# NuclearSMR-1_2.net
KiCad netlist of a schematic drawn in EasyEDA Pro
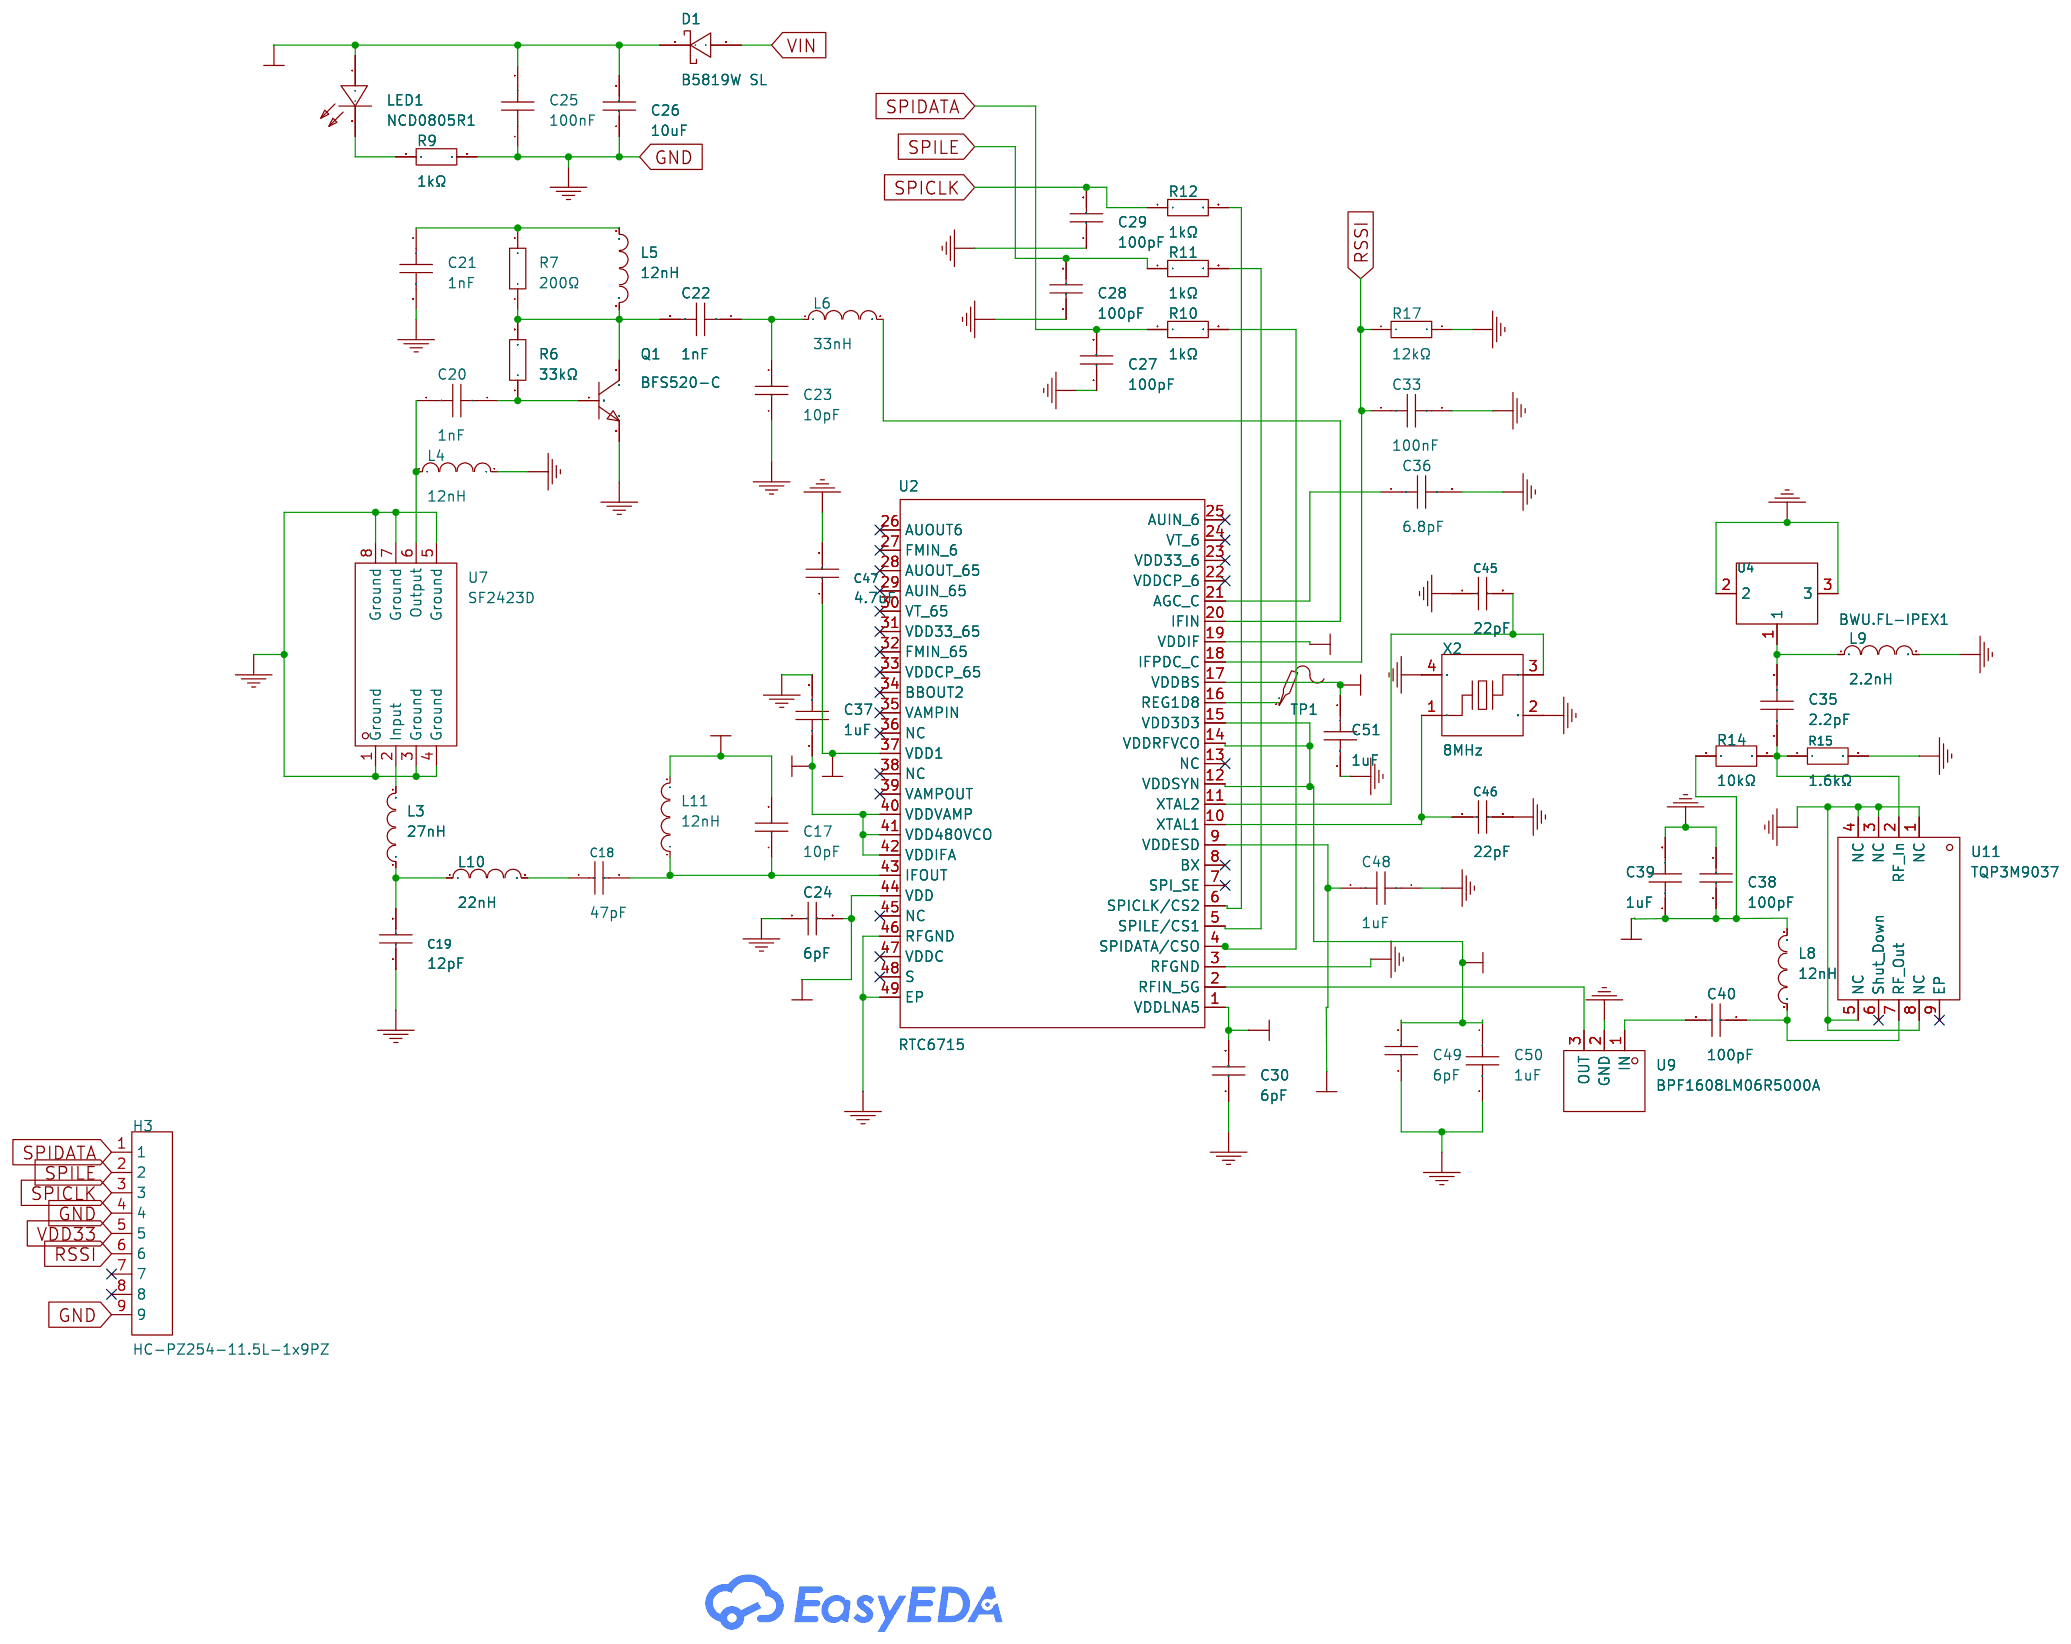
[diagram p0: schematic sheet]

(export (version "E")
  (design (tool "Eeschema 10.0.6"))
  (components
    (comp (ref "C17")
      (value "10pF")
      (footprint "easyedapro:C0402")
      (fields
        (field (name "Manufacturer Part") "CC0402JRNPO9BN100")
        (field (name "Manufacturer") "YAGEO(国巨)")
      )
      (libsource (lib "easyedapro") (part "CC0402JRNPO9BN100"))
    )
    (comp (ref "C18")
      (value "47pF")
      (footprint "easyedapro:C0402")
      (fields
        (field (name "Manufacturer Part") "CC0402JRNPO9BN470")
        (field (name "Manufacturer") "YAGEO(国巨)")
      )
      (libsource (lib "easyedapro") (part "CC0402JRNPO9BN470"))
    )
    (comp (ref "C19")
      (value "12pF")
      (footprint "easyedapro:C0402")
      (fields
        (field (name "Manufacturer Part") "GRM1555C1H120JA01D")
        (field (name "Manufacturer") "muRata(村田)")
      )
      (libsource (lib "easyedapro") (part "GRM1555C1H120JA01D"))
    )
    (comp (ref "C20")
      (value "1nF")
      (footprint "easyedapro:C0402")
      (fields
        (field (name "Manufacturer Part") "GRM155R71H102KA01D")
        (field (name "Manufacturer") "muRata(村田)")
      )
      (libsource (lib "easyedapro") (part "GRM155R71H102KA01D"))
    )
    (comp (ref "C21")
      (value "1nF")
      (footprint "easyedapro:C0402")
      (fields
        (field (name "Manufacturer Part") "GRM155R71H102KA01D")
        (field (name "Manufacturer") "muRata(村田)")
      )
      (libsource (lib "easyedapro") (part "GRM155R71H102KA01D"))
    )
    (comp (ref "C22")
      (value "1nF")
      (footprint "easyedapro:C0402")
      (fields
        (field (name "Manufacturer Part") "GRM155R71H102KA01D")
        (field (name "Manufacturer") "muRata(村田)")
      )
      (libsource (lib "easyedapro") (part "GRM155R71H102KA01D"))
    )
    (comp (ref "C23")
      (value "10pF")
      (footprint "easyedapro:C0402")
      (fields
        (field (name "Manufacturer Part") "GRM1555C1H100JA01D")
        (field (name "Manufacturer") "muRata(村田)")
      )
      (libsource (lib "easyedapro") (part "GRM1555C1H100JA01D"))
    )
    (comp (ref "C24")
      (value "6pF")
      (footprint "easyedapro:C0402")
      (fields (field (name "Manufacturer Part") "0402CG6R0C500NT") (field (name "Manufacturer") "FH(风华)"))
      (libsource (lib "easyedapro") (part "0402CG6R0C500NT"))
    )
    (comp (ref "C25")
      (value "100nF")
      (footprint "easyedapro:C0402")
      (fields
        (field (name "Manufacturer Part") "CL05B104KO5NNNC")
        (field (name "Manufacturer") "SAMSUNG(三星)")
      )
      (libsource (lib "easyedapro") (part "CL05B104KO5NNNC"))
    )
    (comp (ref "C26")
      (value "10uF")
      (fields
        (field (name "Manufacturer Part") "GRM155R60J106ME44D")
        (field (name "Manufacturer") "muRata(村田)")
      )
      (libsource (lib "easyedapro") (part "CL05A106MQ5NUNC"))
    )
    (comp (ref "C27")
      (value "100pF")
      (footprint "easyedapro:C0402")
      (fields
        (field (name "Manufacturer Part") "GRM1555C1H101JA01D")
        (field (name "Manufacturer") "muRata(村田)")
      )
      (libsource (lib "easyedapro") (part "GRM1555C1H101JA01D"))
    )
    (comp (ref "C28")
      (value "100pF")
      (footprint "easyedapro:C0402")
      (fields
        (field (name "Manufacturer Part") "GRM1555C1H101JA01D")
        (field (name "Manufacturer") "muRata(村田)")
      )
      (libsource (lib "easyedapro") (part "GRM1555C1H101JA01D"))
    )
    (comp (ref "C29")
      (value "100pF")
      (footprint "easyedapro:C0402")
      (fields
        (field (name "Manufacturer Part") "GRM1555C1H101JA01D")
        (field (name "Manufacturer") "muRata(村田)")
      )
      (libsource (lib "easyedapro") (part "GRM1555C1H101JA01D"))
    )
    (comp (ref "C30")
      (value "6pF")
      (footprint "easyedapro:C0402")
      (fields (field (name "Manufacturer Part") "0402CG6R0C500NT") (field (name "Manufacturer") "FH(风华)"))
      (libsource (lib "easyedapro") (part "0402CG6R0C500NT"))
    )
    (comp (ref "C33")
      (value "100nF")
      (footprint "easyedapro:C0402")
      (fields
        (field (name "Manufacturer Part") "CL05B104KO5NNNC")
        (field (name "Manufacturer") "SAMSUNG(三星)")
      )
      (libsource (lib "easyedapro") (part "CL05B104KO5NNNC"))
    )
    (comp (ref "C35")
      (value "2.2pF")
      (footprint "easyedapro:C0402")
      (fields
        (field (name "Manufacturer Part") "GJM1555C1H2R2BB01D")
        (field (name "Manufacturer") "muRata(村田)")
      )
      (libsource (lib "easyedapro") (part "GJM1555C1H2R2BB01D"))
    )
    (comp (ref "C36")
      (value "6.8pF")
      (footprint "easyedapro:C0402")
      (fields
        (field (name "Manufacturer Part") "CC0402CRNPO9BN6R8")
        (field (name "Manufacturer") "YAGEO(国巨)")
      )
      (libsource (lib "easyedapro") (part "CC0402CRNPO9BN6R8"))
    )
    (comp (ref "C37")
      (value "1uF")
      (footprint "easyedapro:C0402")
      (fields
        (field (name "Manufacturer Part") "CL05A105KA5NQNC")
        (field (name "Manufacturer") "SAMSUNG(三星)")
      )
      (libsource (lib "easyedapro") (part "CL05A105KA5NQNC"))
    )
    (comp (ref "C38")
      (value "100pF")
      (footprint "easyedapro:C0402")
      (fields
        (field (name "Manufacturer Part") "GRM1555C1H101JA01D")
        (field (name "Manufacturer") "muRata(村田)")
      )
      (libsource (lib "easyedapro") (part "GRM1555C1H101JA01D"))
    )
    (comp (ref "C39")
      (value "1uF")
      (footprint "easyedapro:C0402")
      (fields
        (field (name "Manufacturer Part") "CL05A105KA5NQNC")
        (field (name "Manufacturer") "SAMSUNG(三星)")
      )
      (libsource (lib "easyedapro") (part "CL05A105KA5NQNC"))
    )
    (comp (ref "C40")
      (value "100pF")
      (footprint "easyedapro:C0402")
      (fields
        (field (name "Manufacturer Part") "GRM1555C1H101JA01D")
        (field (name "Manufacturer") "muRata(村田)")
      )
      (libsource (lib "easyedapro") (part "GRM1555C1H101JA01D"))
    )
    (comp (ref "C45")
      (value "22pF")
      (footprint "easyedapro:C0402")
      (fields
        (field (name "Manufacturer Part") "CC0402JRNPO9BN220")
        (field (name "Manufacturer") "YAGEO(国巨)")
      )
      (libsource (lib "easyedapro") (part "CC0402JRNPO9BN220"))
    )
    (comp (ref "C46")
      (value "22pF")
      (footprint "easyedapro:C0402")
      (fields
        (field (name "Manufacturer Part") "CC0402JRNPO9BN220")
        (field (name "Manufacturer") "YAGEO(国巨)")
      )
      (libsource (lib "easyedapro") (part "CC0402JRNPO9BN220"))
    )
    (comp (ref "C47")
      (value "4.7uF")
      (footprint "easyedapro:C0402")
      (fields
        (field (name "Manufacturer Part") "CL05A475MP5NRNC")
        (field (name "Manufacturer") "SAMSUNG(三星)")
      )
      (libsource (lib "easyedapro") (part "CL05A475MP5NRNC"))
    )
    (comp (ref "C48")
      (value "1uF")
      (footprint "easyedapro:C0402")
      (fields
        (field (name "Manufacturer Part") "CL05A105KA5NQNC")
        (field (name "Manufacturer") "SAMSUNG(三星)")
      )
      (libsource (lib "easyedapro") (part "CL05A105KA5NQNC"))
    )
    (comp (ref "C49")
      (value "6pF")
      (footprint "easyedapro:C0402")
      (fields (field (name "Manufacturer Part") "0402CG6R0C500NT") (field (name "Manufacturer") "FH(风华)"))
      (libsource (lib "easyedapro") (part "0402CG6R0C500NT"))
    )
    (comp (ref "C50")
      (value "1uF")
      (footprint "easyedapro:C0402")
      (fields
        (field (name "Manufacturer Part") "CL05A105KA5NQNC")
        (field (name "Manufacturer") "SAMSUNG(三星)")
      )
      (libsource (lib "easyedapro") (part "CL05A105KA5NQNC"))
    )
    (comp (ref "C51")
      (value "1uF")
      (footprint "easyedapro:C0402")
      (fields
        (field (name "Manufacturer Part") "CL05A105KA5NQNC")
        (field (name "Manufacturer") "SAMSUNG(三星)")
      )
      (libsource (lib "easyedapro") (part "CL05A105KA5NQNC"))
    )
    (comp (ref "D1")
      (value "B5819W SL")
      (footprint "easyedapro:SOD-123_L2.7-W1.6-LS3.7-RD-1")
      (description "Forward Voltage (Vf@If):600mV@1A Reverse Voltage (Vr):40V Rectified Current:1A")
      (fields (field (name "Manufacturer") "CJ(江苏长电/长晶)"))
      (libsource (lib "easyedapro") (part "B5819W_C8598"))
    )
    (comp (ref "H3")
      (value "HC-PZ254-11.5L-1x9PZ")
      (footprint "easyedapro:HDR-TH_9P-P2.54-V-M")
      (fields (field (name "Manufacturer") "HC(虹成电子)"))
      (libsource (lib "easyedapro") (part "HC-PZ254-11.5L-1X9PZ"))
    )
    (comp (ref "L3")
      (value "27nH")
      (footprint "easyedapro:L0402-RD")
      (fields (field (name "Manufacturer Part") "LQG15HS27NJ02D") (field (name "Manufacturer") "muRata(村田)"))
      (libsource (lib "easyedapro") (part "LQG15HS27NJ02D"))
    )
    (comp (ref "L4")
      (value "12nH")
      (footprint "easyedapro:L0402")
      (fields (field (name "Manufacturer Part") "LQW15AN12NG00D") (field (name "Manufacturer") "muRata(村田)"))
      (libsource (lib "easyedapro") (part "LQW15AN12NG00D"))
    )
    (comp (ref "L5")
      (value "12nH")
      (footprint "easyedapro:L0402")
      (fields (field (name "Manufacturer Part") "LQW15AN12NG00D") (field (name "Manufacturer") "muRata(村田)"))
      (libsource (lib "easyedapro") (part "LQW15AN12NG00D"))
    )
    (comp (ref "L6")
      (value "33nH")
      (footprint "easyedapro:L0402")
      (fields (field (name "Manufacturer Part") "LQG15HS33NJ02D") (field (name "Manufacturer") "muRata(村田)"))
      (libsource (lib "easyedapro") (part "LQG15HS33NJ02D"))
    )
    (comp (ref "L8")
      (value "12nH")
      (footprint "easyedapro:L0402")
      (fields (field (name "Manufacturer Part") "LQW15AN12NG00D") (field (name "Manufacturer") "muRata(村田)"))
      (libsource (lib "easyedapro") (part "LQW15AN12NG00D"))
    )
    (comp (ref "L9")
      (value "2.2nH")
      (footprint "easyedapro:L0402")
      (fields (field (name "Manufacturer Part") "LQG15HS2N2S02D") (field (name "Manufacturer") "muRata(村田)"))
      (libsource (lib "easyedapro") (part "LQG15HS2N2S02D"))
    )
    (comp (ref "L10")
      (value "22nH")
      (footprint "easyedapro:L0402")
      (fields (field (name "Manufacturer Part") "LQW15AN22NJ00D") (field (name "Manufacturer") "muRata(村田)"))
      (libsource (lib "easyedapro") (part "LQW15AN22NJ00D"))
    )
    (comp (ref "L11")
      (value "12nH")
      (footprint "easyedapro:L0402")
      (fields (field (name "Manufacturer Part") "LQW15AN12NG00D") (field (name "Manufacturer") "muRata(村田)"))
      (libsource (lib "easyedapro") (part "LQW15AN12NG00D"))
    )
    (comp (ref "LED1")
      (value "NCD0805R1")
      (footprint "easyedapro:LED0805-R-RD")
      (fields (field (name "Manufacturer") "国星光电"))
      (libsource (lib "easyedapro") (part "FC-2012HRK-620D"))
    )
    (comp (ref "Q1")
      (value "BFS520-C")
      (footprint "easyedapro:SOT-323-3_L2.0-W1.3-P1.30-LS2.3-BR")
      (fields (field (name "Manufacturer") "Slkor(萨科微)"))
      (libsource (lib "easyedapro") (part "BFS520-C"))
    )
    (comp (ref "R6")
      (value "33kΩ")
      (footprint "easyedapro:R0402")
      (fields (field (name "Manufacturer Part") "RC0402FR-0733KL") (field (name "Manufacturer") "YAGEO(国巨)"))
      (libsource (lib "easyedapro") (part "RC0402FR-0733KL"))
    )
    (comp (ref "R7")
      (value "200Ω")
      (footprint "easyedapro:R0402")
      (fields (field (name "Manufacturer Part") "RC0402FR-07200RL") (field (name "Manufacturer") "YAGEO(国巨)"))
      (libsource (lib "easyedapro") (part "RC0402FR-07200RL"))
    )
    (comp (ref "R9")
      (value "1kΩ")
      (footprint "easyedapro:R0402")
      (fields (field (name "Manufacturer Part") "RC0402FR-071KL") (field (name "Manufacturer") "YAGEO(国巨)"))
      (libsource (lib "easyedapro") (part "RC0402FR-071KL"))
    )
    (comp (ref "R10")
      (value "1kΩ")
      (footprint "easyedapro:R0402")
      (fields (field (name "Manufacturer Part") "RC0402FR-071KL") (field (name "Manufacturer") "YAGEO(国巨)"))
      (libsource (lib "easyedapro") (part "RC0402FR-071KL"))
    )
    (comp (ref "R11")
      (value "1kΩ")
      (footprint "easyedapro:R0402")
      (fields (field (name "Manufacturer Part") "RC0402FR-071KL") (field (name "Manufacturer") "YAGEO(国巨)"))
      (libsource (lib "easyedapro") (part "RC0402FR-071KL"))
    )
    (comp (ref "R12")
      (value "1kΩ")
      (footprint "easyedapro:R0402")
      (fields (field (name "Manufacturer Part") "RC0402FR-071KL") (field (name "Manufacturer") "YAGEO(国巨)"))
      (libsource (lib "easyedapro") (part "RC0402FR-071KL"))
    )
    (comp (ref "R14")
      (value "10kΩ")
      (footprint "easyedapro:R0402")
      (fields (field (name "Manufacturer Part") "FRC0402F1002TS") (field (name "Manufacturer") "FOJAN(富捷)"))
      (libsource (lib "easyedapro") (part "FRC0402F1002TS"))
    )
    (comp (ref "R15")
      (value "1.6kΩ")
      (footprint "easyedapro:R0402")
      (fields
        (field (name "Manufacturer Part") "0402WGF1601TCE")
        (field (name "Manufacturer") "UNI-ROYAL(厚声)")
      )
      (libsource (lib "easyedapro") (part "0402WGF1601TCE"))
    )
    (comp (ref "R17")
      (value "12kΩ")
      (footprint "easyedapro:R0402")
      (fields (field (name "Manufacturer Part") "RTT021202FTH") (field (name "Manufacturer") "RALEC(旺诠)"))
      (libsource (lib "easyedapro") (part "RTT021202FTH"))
    )
    (comp (ref "TP1")
      (value "~")
      (footprint "easyedapro:Test-Point-0.5mm")
      (description "Test Point 测试点")
      (libsource (lib "easyedapro") (part "Test-Point"))
    )
    (comp (ref "U2") (value "RTC6715") (libsource (lib "easyedapro") (part "RTC6715")))
    (comp (ref "U4")
      (value "BWU.FL-IPEX1")
      (footprint "easyedapro:IPEX-SMD_BWIPX-1-001E")
      (fields (field (name "Manufacturer") "BAT WIRELESS(蝙蝠无线)"))
      (libsource (lib "easyedapro") (part "BWU.FL-IPEX1"))
    )
    (comp (ref "U7")
      (value "SF2423D")
      (footprint "easyedapro:FILTER-SMD_8P-L3.8-W3.8-P1.27-BL")
      (fields (field (name "Manufacturer") "muRata(村田)"))
      (libsource (lib "easyedapro") (part "SF2423D"))
    )
    (comp (ref "U9")
      (value "BPF1608LM06R5000A")
      (footprint "easyedapro:FILTER-SMD_3P-L1.6-W0.8-L")
      (description "Bandwidth:800MHz Filter Type:Bandpass Insertion Loss:0.6dB")
      (fields (field (name "Manufacturer") "YAGEO(国巨)"))
      (libsource (lib "easyedapro") (part "BPF1608LM06R5000A"))
    )
    (comp (ref "U11")
      (value "TQP3M9037")
      (footprint "easyedapro:DFN-8_L2.0-W2.0-P0.50-BL-EP")
      (fields (field (name "Manufacturer") "Qorvo"))
      (libsource (lib "easyedapro") (part "TQP3M9037"))
    )
    (comp (ref "X2")
      (value "8MHz")
      (footprint "easyedapro:CRYSTAL-SMD_4P-L3.2-W2.5-BL")
      (fields (field (name "Manufacturer Part") "K3A080001210") (field (name "Manufacturer") "KYX(凯越翔)"))
      (libsource (lib "easyedapro") (part "K3A080001210"))
    )
  )
  (nets
    (net (code "1") (name "GND") (class "Default")
      (node (ref "C19") (pin "1") (pinfunction "1_1") (pintype "input"))
      (node (ref "C21") (pin "2") (pinfunction "2_2") (pintype "unspecified"))
      (node (ref "C23") (pin "1") (pinfunction "1_1") (pintype "input"))
      (node (ref "C24") (pin "1") (pinfunction "1_1") (pintype "input"))
      (node (ref "C25") (pin "1") (pinfunction "1_1") (pintype "unspecified"))
      (node (ref "C26") (pin "1") (pinfunction "1_1") (pintype "input"))
      (node (ref "C27") (pin "1") (pinfunction "1_1") (pintype "input"))
      (node (ref "C28") (pin "1") (pinfunction "1_1") (pintype "input"))
      (node (ref "C29") (pin "1") (pinfunction "1_1") (pintype "input"))
      (node (ref "C30") (pin "1") (pinfunction "1_1") (pintype "input"))
      (node (ref "C33") (pin "2") (pinfunction "2_2") (pintype "unspecified"))
      (node (ref "C36") (pin "2") (pinfunction "2_2") (pintype "unspecified"))
      (node (ref "C37") (pin "2") (pinfunction "2_2") (pintype "unspecified"))
      (node (ref "C38") (pin "2") (pinfunction "2_2") (pintype "input"))
      (node (ref "C39") (pin "2") (pinfunction "2_2") (pintype "unspecified"))
      (node (ref "C45") (pin "1") (pinfunction "1_1") (pintype "input"))
      (node (ref "C46") (pin "2") (pinfunction "2_2") (pintype "input"))
      (node (ref "C47") (pin "2") (pinfunction "2_2") (pintype "input"))
      (node (ref "C48") (pin "1") (pinfunction "1_1") (pintype "unspecified"))
      (node (ref "C49") (pin "1") (pinfunction "1_1") (pintype "input"))
      (node (ref "C50") (pin "2") (pinfunction "2_2") (pintype "unspecified"))
      (node (ref "C51") (pin "2") (pinfunction "2_2") (pintype "unspecified"))
      (node (ref "H3") (pin "4") (pinfunction "4_4") (pintype "unspecified"))
      (node (ref "H3") (pin "9") (pinfunction "9_9") (pintype "unspecified"))
      (node (ref "L4") (pin "2") (pinfunction "2_2") (pintype "unspecified"))
      (node (ref "L9") (pin "2") (pinfunction "2_2") (pintype "unspecified"))
      (node (ref "Q1") (pin "2") (pinfunction "E_2") (pintype "input"))
      (node (ref "R15") (pin "2") (pinfunction "2_2") (pintype "input"))
      (node (ref "R17") (pin "2") (pinfunction "2_2") (pintype "input"))
      (node (ref "R9") (pin "2") (pinfunction "2_2") (pintype "input"))
      (node (ref "U11") (pin "1") (pinfunction "NC_1") (pintype "unspecified"))
      (node (ref "U11") (pin "3") (pinfunction "NC_3") (pintype "unspecified"))
      (node (ref "U11") (pin "4") (pinfunction "NC_4") (pintype "unspecified"))
      (node (ref "U11") (pin "5") (pinfunction "NC_5") (pintype "unspecified"))
      (node (ref "U11") (pin "8") (pinfunction "NC_8") (pintype "unspecified"))
      (node (ref "U2") (pin "3") (pinfunction "RFGND_3") (pintype "unspecified"))
      (node (ref "U2") (pin "46") (pinfunction "RFGND_46") (pintype "unspecified"))
      (node (ref "U2") (pin "49") (pinfunction "EP_49") (pintype "unspecified"))
      (node (ref "U4") (pin "2") (pinfunction "2_2") (pintype "input"))
      (node (ref "U4") (pin "3") (pinfunction "3_3") (pintype "input"))
      (node (ref "U7") (pin "1") (pinfunction "Ground_1") (pintype "unspecified"))
      (node (ref "U7") (pin "3") (pinfunction "Ground_3") (pintype "unspecified"))
      (node (ref "U7") (pin "4") (pinfunction "Ground_4") (pintype "unspecified"))
      (node (ref "U7") (pin "5") (pinfunction "Ground_5") (pintype "unspecified"))
      (node (ref "U7") (pin "7") (pinfunction "Ground_7") (pintype "unspecified"))
      (node (ref "U7") (pin "8") (pinfunction "Ground_8") (pintype "unspecified"))
      (node (ref "U9") (pin "2") (pinfunction "GND_2") (pintype "unspecified"))
      (node (ref "X2") (pin "2") (pinfunction "GND_2") (pintype "input"))
      (node (ref "X2") (pin "4") (pinfunction "GND_4") (pintype "input"))
    )
    (net (code "2") (name "Net-(C18-Pad1)") (class "Default")
      (node (ref "C18") (pin "1") (pinfunction "1_1") (pintype "input"))
      (node (ref "L10") (pin "2") (pinfunction "2_2") (pintype "unspecified"))
    )
    (net (code "3") (name "Net-(C19-Pad2)") (class "Default")
      (node (ref "C19") (pin "2") (pinfunction "2_2") (pintype "input"))
      (node (ref "L10") (pin "1") (pinfunction "1_1") (pintype "unspecified"))
      (node (ref "L3") (pin "1") (pinfunction "1_1") (pintype "unspecified"))
    )
    (net (code "4") (name "Net-(C21-Pad1)") (class "Default")
      (node (ref "C21") (pin "1") (pinfunction "1_1") (pintype "unspecified"))
      (node (ref "L5") (pin "1") (pinfunction "1_1") (pintype "unspecified"))
      (node (ref "R7") (pin "2") (pinfunction "2_2") (pintype "input"))
    )
    (net (code "5") (name "Net-(C22-Pad1)") (class "Default")
      (node (ref "C22") (pin "1") (pinfunction "1_1") (pintype "unspecified"))
      (node (ref "C23") (pin "2") (pinfunction "2_2") (pintype "input"))
      (node (ref "L6") (pin "1") (pinfunction "1_1") (pintype "unspecified"))
    )
    (net (code "6") (name "Net-(C35-Pad2)") (class "Default")
      (node (ref "C35") (pin "2") (pinfunction "2_2") (pintype "unspecified"))
      (node (ref "L9") (pin "1") (pinfunction "1_1") (pintype "unspecified"))
      (node (ref "U4") (pin "1") (pinfunction "1_1") (pintype "input"))
    )
    (net (code "7") (name "Net-(LED1--)") (class "Default")
      (node (ref "LED1") (pin "2") (pinfunction "-_2") (pintype "unspecified"))
      (node (ref "R9") (pin "1") (pinfunction "1_1") (pintype "input"))
    )
    (net (code "8") (name "Net-(Q1-B)") (class "Default")
      (node (ref "C20") (pin "1") (pinfunction "1_1") (pintype "unspecified"))
      (node (ref "Q1") (pin "1") (pinfunction "B_1") (pintype "input"))
      (node (ref "R6") (pin "1") (pinfunction "1_1") (pintype "input"))
    )
    (net (code "9") (name "Net-(Q1-C)") (class "Default")
      (node (ref "C22") (pin "2") (pinfunction "2_2") (pintype "unspecified"))
      (node (ref "L5") (pin "2") (pinfunction "2_2") (pintype "unspecified"))
      (node (ref "Q1") (pin "3") (pinfunction "C_3") (pintype "input"))
      (node (ref "R6") (pin "2") (pinfunction "2_2") (pintype "input"))
      (node (ref "R7") (pin "1") (pinfunction "1_1") (pintype "input"))
    )
    (net (code "10") (name "Net-(U2-AGC_C)") (class "Default")
      (node (ref "C36") (pin "1") (pinfunction "1_1") (pintype "unspecified"))
      (node (ref "U2") (pin "21") (pinfunction "AGC_C_21") (pintype "unspecified"))
    )
    (net (code "11") (name "Net-(U2-IFIN)") (class "Default")
      (node (ref "L6") (pin "2") (pinfunction "2_2") (pintype "unspecified"))
      (node (ref "U2") (pin "20") (pinfunction "IFIN_20") (pintype "unspecified"))
    )
    (net (code "12") (name "Net-(U2-IFOUT)") (class "Default")
      (node (ref "C17") (pin "1") (pinfunction "1_1") (pintype "input"))
      (node (ref "C18") (pin "2") (pinfunction "2_2") (pintype "input"))
      (node (ref "L11") (pin "1") (pinfunction "1_1") (pintype "unspecified"))
      (node (ref "U2") (pin "43") (pinfunction "IFOUT_43") (pintype "unspecified"))
    )
    (net (code "13") (name "Net-(U2-REG1D8)") (class "Default")
      (node (ref "TP1") (pin "1") (pinfunction "1_1") (pintype "unspecified"))
      (node (ref "U2") (pin "16") (pinfunction "REG1D8_16") (pintype "unspecified"))
    )
    (net (code "14") (name "Net-(U2-RFIN_5G)") (class "Default")
      (node (ref "U2") (pin "2") (pinfunction "RFIN_5G_2") (pintype "unspecified"))
      (node (ref "U9") (pin "3") (pinfunction "OUT_3") (pintype "unspecified"))
    )
    (net (code "15") (name "Net-(U2-SPICLK{slash}CS2)") (class "Default")
      (node (ref "R12") (pin "2") (pinfunction "2_2") (pintype "input"))
      (node (ref "U2") (pin "6") (pinfunction "SPICLK/CS2_6") (pintype "unspecified"))
    )
    (net (code "16") (name "Net-(U2-SPIDATA{slash}CSO)") (class "Default")
      (node (ref "R10") (pin "2") (pinfunction "2_2") (pintype "input"))
      (node (ref "U2") (pin "4") (pinfunction "SPIDATA/CSO_4") (pintype "unspecified"))
    )
    (net (code "17") (name "Net-(U2-SPILE{slash}CS1)") (class "Default")
      (node (ref "R11") (pin "2") (pinfunction "2_2") (pintype "input"))
      (node (ref "U2") (pin "5") (pinfunction "SPILE/CS1_5") (pintype "unspecified"))
    )
    (net (code "18") (name "Net-(U2-XTAL1)") (class "Default")
      (node (ref "C46") (pin "1") (pinfunction "1_1") (pintype "input"))
      (node (ref "U2") (pin "10") (pinfunction "XTAL1_10") (pintype "unspecified"))
      (node (ref "X2") (pin "1") (pinfunction "1_1") (pintype "input"))
    )
    (net (code "19") (name "Net-(U2-XTAL2)") (class "Default")
      (node (ref "C45") (pin "2") (pinfunction "2_2") (pintype "input"))
      (node (ref "U2") (pin "11") (pinfunction "XTAL2_11") (pintype "unspecified"))
      (node (ref "X2") (pin "3") (pinfunction "3_3") (pintype "input"))
    )
    (net (code "20") (name "Net-(U7-Input)") (class "Default")
      (node (ref "L3") (pin "2") (pinfunction "2_2") (pintype "unspecified"))
      (node (ref "U7") (pin "2") (pinfunction "Input_2") (pintype "unspecified"))
    )
    (net (code "21") (name "Net-(U7-Output)") (class "Default")
      (node (ref "C20") (pin "2") (pinfunction "2_2") (pintype "unspecified"))
      (node (ref "L4") (pin "1") (pinfunction "1_1") (pintype "unspecified"))
      (node (ref "U7") (pin "6") (pinfunction "Output_6") (pintype "unspecified"))
    )
    (net (code "22") (name "Net-(U9-IN)") (class "Default")
      (node (ref "C40") (pin "2") (pinfunction "2_2") (pintype "input"))
      (node (ref "U9") (pin "1") (pinfunction "IN_1") (pintype "unspecified"))
    )
    (net (code "23") (name "Net-(U11-RF_In)") (class "Default")
      (node (ref "C35") (pin "1") (pinfunction "1_1") (pintype "unspecified"))
      (node (ref "R14") (pin "2") (pinfunction "2_2") (pintype "unspecified"))
      (node (ref "R15") (pin "1") (pinfunction "1_1") (pintype "input"))
      (node (ref "U11") (pin "2") (pinfunction "RF_In_2") (pintype "unspecified"))
    )
    (net (code "24") (name "Net-(U11-RF_Out)") (class "Default")
      (node (ref "C40") (pin "1") (pinfunction "1_1") (pintype "input"))
      (node (ref "L8") (pin "1") (pinfunction "1_1") (pintype "unspecified"))
      (node (ref "U11") (pin "7") (pinfunction "RF_Out_7") (pintype "unspecified"))
    )
    (net (code "25") (name "RSSI") (class "Default")
      (node (ref "C33") (pin "1") (pinfunction "1_1") (pintype "unspecified"))
      (node (ref "H3") (pin "6") (pinfunction "6_6") (pintype "unspecified"))
      (node (ref "R17") (pin "1") (pinfunction "1_1") (pintype "input"))
      (node (ref "U2") (pin "18") (pinfunction "IFPDC_C_18") (pintype "unspecified"))
    )
    (net (code "26") (name "SPICLK") (class "Default")
      (node (ref "C29") (pin "2") (pinfunction "2_2") (pintype "input"))
      (node (ref "H3") (pin "3") (pinfunction "3_3") (pintype "unspecified"))
      (node (ref "R12") (pin "1") (pinfunction "1_1") (pintype "input"))
    )
    (net (code "27") (name "SPIDATA") (class "Default")
      (node (ref "C27") (pin "2") (pinfunction "2_2") (pintype "input"))
      (node (ref "H3") (pin "1") (pinfunction "1_1") (pintype "unspecified"))
      (node (ref "R10") (pin "1") (pinfunction "1_1") (pintype "input"))
    )
    (net (code "28") (name "SPILE") (class "Default")
      (node (ref "C28") (pin "2") (pinfunction "2_2") (pintype "input"))
      (node (ref "H3") (pin "2") (pinfunction "2_2") (pintype "unspecified"))
      (node (ref "R11") (pin "1") (pinfunction "1_1") (pintype "input"))
    )
    (net (code "29") (name "VDD33") (class "Default")
      (node (ref "C17") (pin "2") (pinfunction "2_2") (pintype "input"))
      (node (ref "C24") (pin "2") (pinfunction "2_2") (pintype "input"))
      (node (ref "C25") (pin "2") (pinfunction "2_2") (pintype "unspecified"))
      (node (ref "C26") (pin "2") (pinfunction "2_2") (pintype "input"))
      (node (ref "C30") (pin "2") (pinfunction "2_2") (pintype "input"))
      (node (ref "C37") (pin "1") (pinfunction "1_1") (pintype "unspecified"))
      (node (ref "C38") (pin "1") (pinfunction "1_1") (pintype "input"))
      (node (ref "C39") (pin "1") (pinfunction "1_1") (pintype "unspecified"))
      (node (ref "C47") (pin "1") (pinfunction "1_1") (pintype "input"))
      (node (ref "C48") (pin "2") (pinfunction "2_2") (pintype "unspecified"))
      (node (ref "C49") (pin "2") (pinfunction "2_2") (pintype "input"))
      (node (ref "C50") (pin "1") (pinfunction "1_1") (pintype "unspecified"))
      (node (ref "C51") (pin "1") (pinfunction "1_1") (pintype "unspecified"))
      (node (ref "D1") (pin "1") (pinfunction "-_1") (pintype "unspecified"))
      (node (ref "H3") (pin "5") (pinfunction "5_5") (pintype "unspecified"))
      (node (ref "L11") (pin "2") (pinfunction "2_2") (pintype "unspecified"))
      (node (ref "L8") (pin "2") (pinfunction "2_2") (pintype "unspecified"))
      (node (ref "LED1") (pin "1") (pinfunction "+_1") (pintype "unspecified"))
      (node (ref "R14") (pin "1") (pinfunction "1_1") (pintype "unspecified"))
      (node (ref "U2") (pin "1") (pinfunction "VDDLNA5_1") (pintype "unspecified"))
      (node (ref "U2") (pin "12") (pinfunction "VDDSYN_12") (pintype "unspecified"))
      (node (ref "U2") (pin "14") (pinfunction "VDDRFVCO_14") (pintype "unspecified"))
      (node (ref "U2") (pin "15") (pinfunction "VDD3D3_15") (pintype "unspecified"))
      (node (ref "U2") (pin "17") (pinfunction "VDDBS_17") (pintype "unspecified"))
      (node (ref "U2") (pin "19") (pinfunction "VDDIF_19") (pintype "unspecified"))
      (node (ref "U2") (pin "37") (pinfunction "VDD1_37") (pintype "unspecified"))
      (node (ref "U2") (pin "40") (pinfunction "VDDVAMP_40") (pintype "unspecified"))
      (node (ref "U2") (pin "41") (pinfunction "VDD480VCO_41") (pintype "unspecified"))
      (node (ref "U2") (pin "42") (pinfunction "VDDIFA_42") (pintype "unspecified"))
      (node (ref "U2") (pin "44") (pinfunction "VDD_44") (pintype "unspecified"))
      (node (ref "U2") (pin "9") (pinfunction "VDDESD_9") (pintype "unspecified"))
    )
    (net (code "30") (name "VIN") (class "Default")
      (node (ref "D1") (pin "2") (pinfunction "+_2") (pintype "unspecified"))
    )
    (net (code "31") (name "unconnected-(H3-Pad7)") (class "Default")
      (node (ref "H3") (pin "7") (pinfunction "7_7") (pintype "unspecified+no_connect"))
    )
    (net (code "32") (name "unconnected-(H3-Pad8)") (class "Default")
      (node (ref "H3") (pin "8") (pinfunction "8_8") (pintype "unspecified+no_connect"))
    )
    (net (code "33") (name "unconnected-(U2-AUIN_6-Pad25)") (class "Default")
      (node (ref "U2") (pin "25") (pinfunction "AUIN_6_25") (pintype "unspecified+no_connect"))
    )
    (net (code "34") (name "unconnected-(U2-AUIN_65-Pad29)") (class "Default")
      (node (ref "U2") (pin "29") (pinfunction "AUIN_65_29") (pintype "unspecified+no_connect"))
    )
    (net (code "35") (name "unconnected-(U2-AUOUT6-Pad26)") (class "Default")
      (node (ref "U2") (pin "26") (pinfunction "AUOUT6_26") (pintype "unspecified+no_connect"))
    )
    (net (code "36") (name "unconnected-(U2-AUOUT_65-Pad28)") (class "Default")
      (node (ref "U2") (pin "28") (pinfunction "AUOUT_65_28") (pintype "unspecified+no_connect"))
    )
    (net (code "37") (name "unconnected-(U2-BBOUT2-Pad34)") (class "Default")
      (node (ref "U2") (pin "34") (pinfunction "BBOUT2_34") (pintype "unspecified+no_connect"))
    )
    (net (code "38") (name "unconnected-(U2-BX-Pad8)") (class "Default")
      (node (ref "U2") (pin "8") (pinfunction "BX_8") (pintype "unspecified+no_connect"))
    )
    (net (code "39") (name "unconnected-(U2-FMIN_6-Pad27)") (class "Default")
      (node (ref "U2") (pin "27") (pinfunction "FMIN_6_27") (pintype "unspecified+no_connect"))
    )
    (net (code "40") (name "unconnected-(U2-FMIN_65-Pad32)") (class "Default")
      (node (ref "U2") (pin "32") (pinfunction "FMIN_65_32") (pintype "unspecified+no_connect"))
    )
    (net (code "41") (name "unconnected-(U2-NC-Pad13)") (class "Default")
      (node (ref "U2") (pin "13") (pinfunction "NC_13") (pintype "unspecified+no_connect"))
    )
    (net (code "42") (name "unconnected-(U2-NC-Pad36)") (class "Default")
      (node (ref "U2") (pin "36") (pinfunction "NC_36") (pintype "unspecified+no_connect"))
    )
    (net (code "43") (name "unconnected-(U2-NC-Pad38)") (class "Default")
      (node (ref "U2") (pin "38") (pinfunction "NC_38") (pintype "unspecified+no_connect"))
    )
    (net (code "44") (name "unconnected-(U2-NC-Pad45)") (class "Default")
      (node (ref "U2") (pin "45") (pinfunction "NC_45") (pintype "unspecified+no_connect"))
    )
    (net (code "45") (name "unconnected-(U2-S-Pad48)") (class "Default")
      (node (ref "U2") (pin "48") (pinfunction "S_48") (pintype "unspecified+no_connect"))
    )
    (net (code "46") (name "unconnected-(U2-SPI_SE-Pad7)") (class "Default")
      (node (ref "U2") (pin "7") (pinfunction "SPI_SE_7") (pintype "unspecified+no_connect"))
    )
    (net (code "47") (name "unconnected-(U2-VAMPIN-Pad35)") (class "Default")
      (node (ref "U2") (pin "35") (pinfunction "VAMPIN_35") (pintype "unspecified+no_connect"))
    )
    (net (code "48") (name "unconnected-(U2-VAMPOUT-Pad39)") (class "Default")
      (node (ref "U2") (pin "39") (pinfunction "VAMPOUT_39") (pintype "unspecified+no_connect"))
    )
    (net (code "49") (name "unconnected-(U2-VDD33_6-Pad23)") (class "Default")
      (node (ref "U2") (pin "23") (pinfunction "VDD33_6_23") (pintype "unspecified+no_connect"))
    )
    (net (code "50") (name "unconnected-(U2-VDD33_65-Pad31)") (class "Default")
      (node (ref "U2") (pin "31") (pinfunction "VDD33_65_31") (pintype "unspecified+no_connect"))
    )
    (net (code "51") (name "unconnected-(U2-VDDC-Pad47)") (class "Default")
      (node (ref "U2") (pin "47") (pinfunction "VDDC_47") (pintype "unspecified+no_connect"))
    )
    (net (code "52") (name "unconnected-(U2-VDDCP_6-Pad22)") (class "Default")
      (node (ref "U2") (pin "22") (pinfunction "VDDCP_6_22") (pintype "unspecified+no_connect"))
    )
    (net (code "53") (name "unconnected-(U2-VDDCP_65-Pad33)") (class "Default")
      (node (ref "U2") (pin "33") (pinfunction "VDDCP_65_33") (pintype "unspecified+no_connect"))
    )
    (net (code "54") (name "unconnected-(U2-VT_6-Pad24)") (class "Default")
      (node (ref "U2") (pin "24") (pinfunction "VT_6_24") (pintype "unspecified+no_connect"))
    )
    (net (code "55") (name "unconnected-(U2-VT_65-Pad30)") (class "Default")
      (node (ref "U2") (pin "30") (pinfunction "VT_65_30") (pintype "unspecified+no_connect"))
    )
    (net (code "56") (name "unconnected-(U11-EP-Pad9)") (class "Default")
      (node (ref "U11") (pin "9") (pinfunction "EP_9") (pintype "unspecified+no_connect"))
    )
    (net (code "57") (name "unconnected-(U11-Shut_Down-Pad6)") (class "Default")
      (node (ref "U11") (pin "6") (pinfunction "Shut_Down_6") (pintype "unspecified+no_connect"))
    )
  )
)
